# NANO_HEADER.net
KiCad netlist of a schematic drawn in Altium Designer
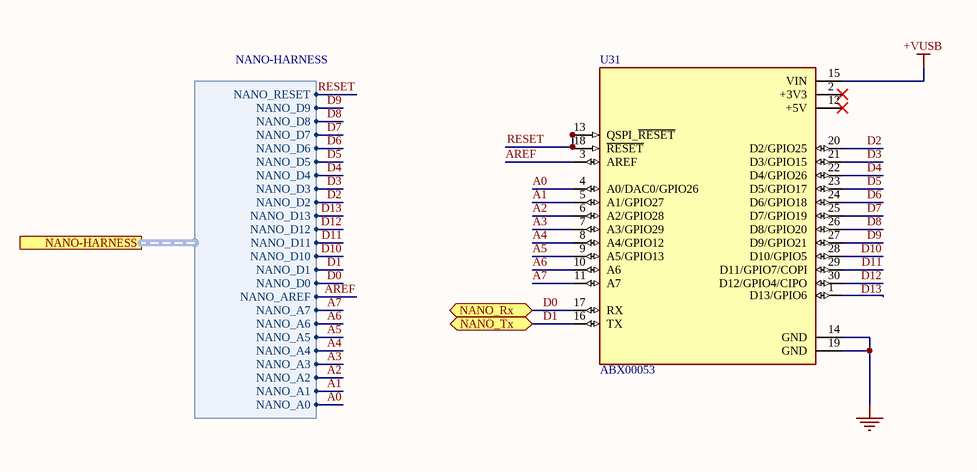
[diagram p0: NANO_HEADER.SchDoc]

(export (version "E")
  (design (tool "Eeschema 10.0.6"))
  (components
    (comp (ref "U31")
      (value "ABX00053")
      (footprint "ABX00053:MODULE_ABX00053")
      (fields (field (name "MF") "Arduino") (field (name "DIGI-KEY_PART_NUMBER") "1050-ABX00053-ND"))
      (libsource (lib "ABX00053") (part "ABX00053"))
    )
  )
  (nets
    (net (code "2") (name "+VUSB") (class "Default")
      (node (ref "U31") (pin "15") (pinfunction "VIN_15") (pintype "power_in"))
    )
    (net (code "3") (name "/A0") (class "Default")
      (node (ref "U31") (pin "4") (pinfunction "A0/DAC0/GPIO26_4") (pintype "bidirectional"))
    )
    (net (code "4") (name "/A1") (class "Default")
      (node (ref "U31") (pin "5") (pinfunction "A1/GPIO27_5") (pintype "bidirectional"))
    )
    (net (code "5") (name "/A2") (class "Default")
      (node (ref "U31") (pin "6") (pinfunction "A2/GPIO28_6") (pintype "bidirectional"))
    )
    (net (code "6") (name "/A3") (class "Default")
      (node (ref "U31") (pin "7") (pinfunction "A3/GPIO29_7") (pintype "bidirectional"))
    )
    (net (code "7") (name "/A4") (class "Default")
      (node (ref "U31") (pin "8") (pinfunction "A4/GPIO12_8") (pintype "bidirectional"))
    )
    (net (code "8") (name "/A5") (class "Default")
      (node (ref "U31") (pin "9") (pinfunction "A5/GPIO13_9") (pintype "bidirectional"))
    )
    (net (code "9") (name "/A6") (class "Default")
      (node (ref "U31") (pin "10") (pinfunction "A6_10") (pintype "bidirectional"))
    )
    (net (code "10") (name "/A7") (class "Default")
      (node (ref "U31") (pin "11") (pinfunction "A7_11") (pintype "bidirectional"))
    )
    (net (code "11") (name "/AREF") (class "Default")
      (node (ref "U31") (pin "3") (pinfunction "AREF_3") (pintype "bidirectional"))
    )
    (net (code "12") (name "/D0") (class "Default")
      (node (ref "U31") (pin "17") (pinfunction "RX_17") (pintype "bidirectional"))
    )
    (net (code "13") (name "/D1") (class "Default")
      (node (ref "U31") (pin "16") (pinfunction "TX_16") (pintype "bidirectional"))
    )
    (net (code "14") (name "/D2") (class "Default")
      (node (ref "U31") (pin "20") (pinfunction "D2/GPIO25_20") (pintype "bidirectional"))
    )
    (net (code "15") (name "/D3") (class "Default")
      (node (ref "U31") (pin "21") (pinfunction "D3/GPIO15_21") (pintype "bidirectional"))
    )
    (net (code "16") (name "/D4") (class "Default")
      (node (ref "U31") (pin "22") (pinfunction "D4/GPIO26_22") (pintype "bidirectional"))
    )
    (net (code "17") (name "/D5") (class "Default")
      (node (ref "U31") (pin "23") (pinfunction "D5/GPIO17_23") (pintype "bidirectional"))
    )
    (net (code "18") (name "/D6") (class "Default")
      (node (ref "U31") (pin "24") (pinfunction "D6/GPIO18_24") (pintype "bidirectional"))
    )
    (net (code "19") (name "/D7") (class "Default")
      (node (ref "U31") (pin "25") (pinfunction "D7/GPIO19_25") (pintype "bidirectional"))
    )
    (net (code "20") (name "/D8") (class "Default")
      (node (ref "U31") (pin "26") (pinfunction "D8/GPIO20_26") (pintype "bidirectional"))
    )
    (net (code "21") (name "/D9") (class "Default")
      (node (ref "U31") (pin "27") (pinfunction "D9/GPIO21_27") (pintype "bidirectional"))
    )
    (net (code "22") (name "/D10") (class "Default")
      (node (ref "U31") (pin "28") (pinfunction "D10/GPIO5_28") (pintype "bidirectional"))
    )
    (net (code "23") (name "/D11") (class "Default")
      (node (ref "U31") (pin "29") (pinfunction "D11/GPIO7/COPI_29") (pintype "bidirectional"))
    )
    (net (code "24") (name "/D12") (class "Default")
      (node (ref "U31") (pin "30") (pinfunction "D12/GPIO4/CIPO_30") (pintype "bidirectional"))
    )
    (net (code "25") (name "/D13") (class "Default")
      (node (ref "U31") (pin "1") (pinfunction "D13/GPIO6_1") (pintype "bidirectional"))
    )
    (net (code "26") (name "/RESET") (class "Default")
      (node (ref "U31") (pin "13") (pinfunction "QSPI_~{RESET}_13") (pintype "input"))
      (node (ref "U31") (pin "18") (pinfunction "~{RESET}_18") (pintype "input"))
    )
    (net (code "28") (name "GND") (class "Default")
      (node (ref "U31") (pin "14") (pinfunction "GND_14") (pintype "power_in"))
      (node (ref "U31") (pin "19") (pinfunction "GND_19") (pintype "power_in"))
    )
    (net (code "29") (name "unconnected-(U31-+3V3-Pad2)") (class "Default")
      (node (ref "U31") (pin "2") (pinfunction "+3V3_2") (pintype "power_in+no_connect"))
    )
    (net (code "30") (name "unconnected-(U31-+5V-Pad12)") (class "Default")
      (node (ref "U31") (pin "12") (pinfunction "+5V_12") (pintype "power_in+no_connect"))
    )
  )
)
